# THTfeather.net
KiCad netlist of a schematic drawn in EAGLE
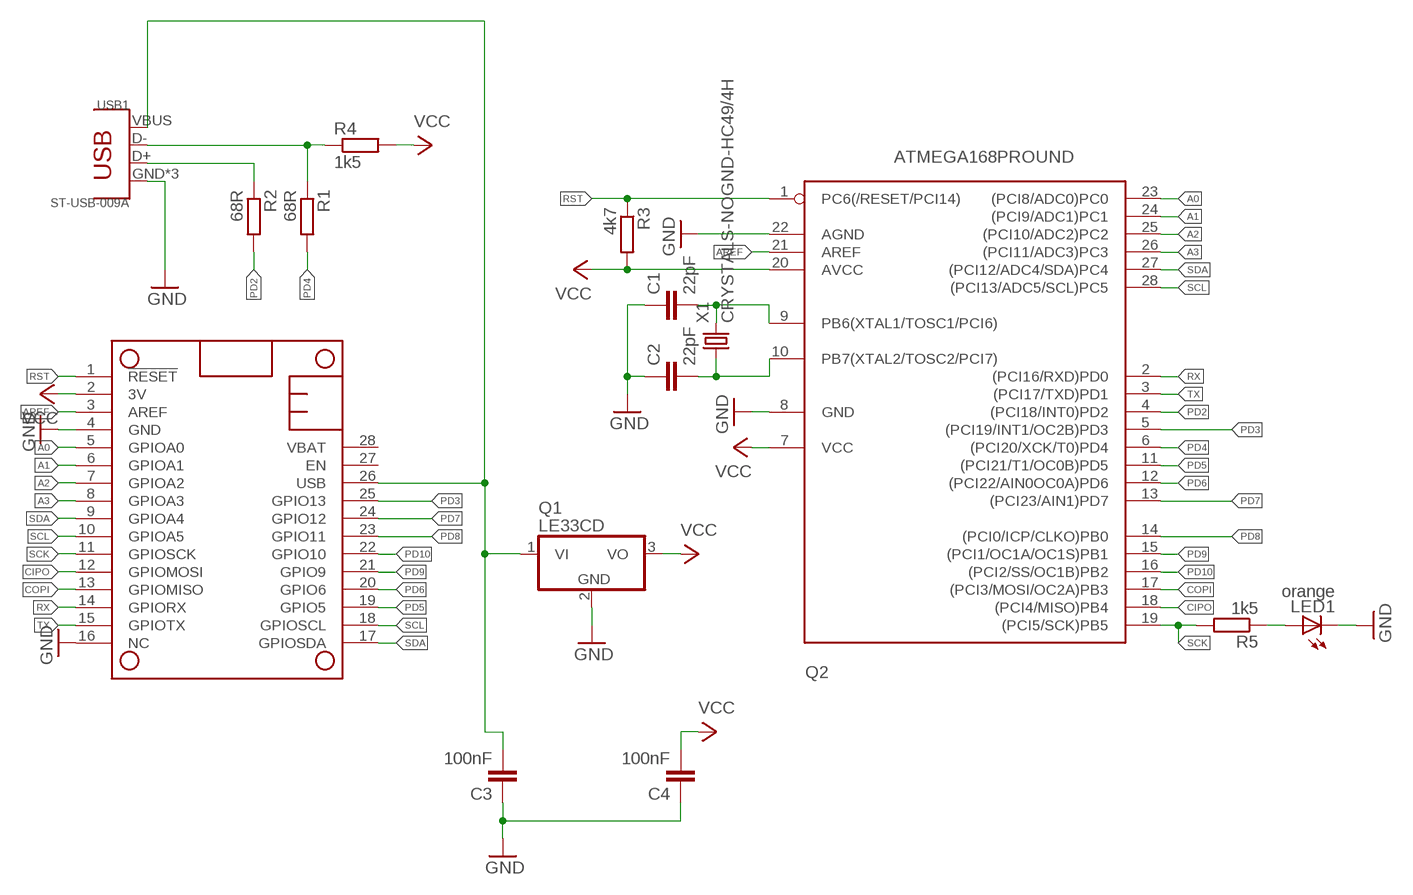
[diagram p0: schematic, sheet 1]

(export (version "E")
  (design (tool "Eeschema 10.0.6"))
  (components
    (comp (ref "C1")
      (value "22pF")
      (footprint "eagle-import:C025-025X050")
      (libsource (lib "eagle-import") (part "C-EU025-025X050"))
    )
    (comp (ref "C2")
      (value "22pF")
      (footprint "eagle-import:C025-025X050")
      (libsource (lib "eagle-import") (part "C-EU025-025X050"))
    )
    (comp (ref "C3")
      (value "100nF")
      (footprint "eagle-import:C025-025X050")
      (libsource (lib "eagle-import") (part "C-EU025-025X050"))
    )
    (comp (ref "C4")
      (value "100nF")
      (footprint "eagle-import:C025-025X050")
      (libsource (lib "eagle-import") (part "C-EU025-025X050"))
    )
    (comp (ref "LED1")
      (value "orange")
      (footprint "eagle-import:LED3MM")
      (libsource (lib "eagle-import") (part "LED3MM"))
    )
    (comp (ref "MS1")
      (value "FEATHERWING_NODIM")
      (footprint "eagle-import:FEATHERWING_DIM")
      (libsource (lib "eagle-import") (part "FEATHERWING_NODIM"))
    )
    (comp (ref "Q1")
      (value "LE33CD")
      (footprint "eagle-import:TO92")
      (libsource (lib "eagle-import") (part "78L33"))
    )
    (comp (ref "Q2")
      (value "ATMEGA168PROUND")
      (footprint "eagle-import:DIL28-3-ROUND")
      (libsource (lib "eagle-import") (part "ATMEGA168PROUND"))
    )
    (comp (ref "R1")
      (value "68R")
      (footprint "eagle-import:0204_5")
      (libsource (lib "eagle-import") (part "R-EU_0204/5"))
    )
    (comp (ref "R2")
      (value "68R")
      (footprint "eagle-import:0204_5")
      (libsource (lib "eagle-import") (part "R-EU_0204/5"))
    )
    (comp (ref "R3")
      (value "4k7")
      (footprint "eagle-import:0204_5")
      (libsource (lib "eagle-import") (part "R-EU_0204/5"))
    )
    (comp (ref "R4")
      (value "1k5")
      (footprint "eagle-import:0204_5")
      (libsource (lib "eagle-import") (part "R-EU_0204/5"))
    )
    (comp (ref "R5")
      (value "1k5")
      (footprint "eagle-import:0204_5")
      (libsource (lib "eagle-import") (part "R-EU_0204/5"))
    )
    (comp (ref "USB1")
      (value "ST-USB-009A")
      (footprint "eagle-import:USB4+2-2.5-90D")
      (libsource (lib "eagle-import") (part "DIP-USB-B-TYPE-FMAL(4+2P-2.5-90D)"))
    )
    (comp (ref "X1")
      (value "CRYSTALS-NOGND-HC49/4H")
      (footprint "eagle-import:HC49")
      (libsource (lib "eagle-import") (part "CRYSTALS-NOGND-HC49/4H"))
    )
  )
  (nets
    (net (code "1") (name "/VBAT") (class "Default")
      (node (ref "MS1") (pin "28") (pinfunction "VBAT_28") (pintype "power_in"))
    )
    (net (code "2") (name "A0") (class "Default")
      (node (ref "MS1") (pin "5") (pinfunction "GPIOA0_5") (pintype "bidirectional"))
      (node (ref "Q2") (pin "23") (pinfunction "(PCI8/ADC0)PC0_23") (pintype "bidirectional"))
    )
    (net (code "3") (name "A1") (class "Default")
      (node (ref "MS1") (pin "6") (pinfunction "GPIOA1_6") (pintype "bidirectional"))
      (node (ref "Q2") (pin "24") (pinfunction "(PCI9/ADC1)PC1_24") (pintype "bidirectional"))
    )
    (net (code "4") (name "A2") (class "Default")
      (node (ref "MS1") (pin "7") (pinfunction "GPIOA2_7") (pintype "bidirectional"))
      (node (ref "Q2") (pin "25") (pinfunction "(PCI10/ADC2)PC2_25") (pintype "bidirectional"))
    )
    (net (code "5") (name "A3") (class "Default")
      (node (ref "MS1") (pin "8") (pinfunction "GPIOA3_8") (pintype "bidirectional"))
      (node (ref "Q2") (pin "26") (pinfunction "(PCI11/ADC3)PC3_26") (pintype "bidirectional"))
    )
    (net (code "6") (name "AREF") (class "Default")
      (node (ref "MS1") (pin "3") (pinfunction "AREF_3") (pintype "passive"))
      (node (ref "Q2") (pin "21") (pinfunction "AREF_21") (pintype "bidirectional"))
    )
    (net (code "7") (name "CIPO") (class "Default")
      (node (ref "MS1") (pin "12") (pinfunction "GPIOMOSI_12") (pintype "bidirectional"))
      (node (ref "Q2") (pin "18") (pinfunction "(PCI4/MISO)PB4_18") (pintype "bidirectional"))
    )
    (net (code "8") (name "COPI") (class "Default")
      (node (ref "MS1") (pin "13") (pinfunction "GPIOMISO_13") (pintype "bidirectional"))
      (node (ref "Q2") (pin "17") (pinfunction "(PCI3/MOSI/OC2A)PB3_17") (pintype "bidirectional"))
    )
    (net (code "9") (name "GND") (class "Default")
      (node (ref "C1") (pin "1") (pinfunction "1_1") (pintype "passive"))
      (node (ref "C2") (pin "1") (pinfunction "1_1") (pintype "passive"))
      (node (ref "C3") (pin "1") (pinfunction "1_1") (pintype "passive"))
      (node (ref "C4") (pin "1") (pinfunction "1_1") (pintype "passive"))
      (node (ref "LED1") (pin "K") (pinfunction "C_K") (pintype "passive"))
      (node (ref "MS1") (pin "16") (pinfunction "NC_16") (pintype "passive"))
      (node (ref "MS1") (pin "4") (pinfunction "GND_4") (pintype "power_in"))
      (node (ref "Q1") (pin "2") (pinfunction "GND_2") (pintype "passive"))
      (node (ref "Q2") (pin "22") (pinfunction "AGND_22") (pintype "bidirectional"))
      (node (ref "Q2") (pin "8") (pinfunction "GND_8") (pintype "bidirectional"))
      (node (ref "USB1") (pin "GND") (pinfunction "4_GND") (pintype "bidirectional"))
      (node (ref "USB1") (pin "S1") (pinfunction "4_S1") (pintype "bidirectional"))
      (node (ref "USB1") (pin "S2") (pinfunction "4_S2") (pintype "bidirectional"))
    )
    (net (code "10") (name "Net-(LED1-PadA)") (class "Default")
      (node (ref "LED1") (pin "A") (pinfunction "A_A") (pintype "passive"))
      (node (ref "R5") (pin "1") (pinfunction "1_1") (pintype "passive"))
    )
    (net (code "11") (name "Net-(MS1-USB)") (class "Default")
      (node (ref "C3") (pin "2") (pinfunction "2_2") (pintype "passive"))
      (node (ref "MS1") (pin "26") (pinfunction "USB_26") (pintype "power_in"))
      (node (ref "Q1") (pin "1") (pinfunction "VI_1") (pintype "input"))
      (node (ref "USB1") (pin "VBUS") (pinfunction "1_VBUS") (pintype "bidirectional"))
    )
    (net (code "12") (name "Net-(Q2-PB6(XTAL1{slash}TOSC1{slash}PCI6))") (class "Default")
      (node (ref "C1") (pin "2") (pinfunction "2_2") (pintype "passive"))
      (node (ref "Q2") (pin "9") (pinfunction "PB6(XTAL1/TOSC1/PCI6)_9") (pintype "bidirectional"))
      (node (ref "X1") (pin "2") (pinfunction "2_2") (pintype "passive"))
    )
    (net (code "13") (name "Net-(Q2-PB7(XTAL2{slash}TOSC2{slash}PCI7))") (class "Default")
      (node (ref "C2") (pin "2") (pinfunction "2_2") (pintype "passive"))
      (node (ref "Q2") (pin "10") (pinfunction "PB7(XTAL2/TOSC2/PCI7)_10") (pintype "bidirectional"))
      (node (ref "X1") (pin "1") (pinfunction "1_1") (pintype "passive"))
    )
    (net (code "14") (name "Net-(USB1-2)") (class "Default")
      (node (ref "R1") (pin "1") (pinfunction "1_1") (pintype "passive"))
      (node (ref "R4") (pin "1") (pinfunction "1_1") (pintype "passive"))
      (node (ref "USB1") (pin "D-") (pinfunction "2_D-") (pintype "bidirectional"))
    )
    (net (code "15") (name "Net-(USB1-3)") (class "Default")
      (node (ref "R2") (pin "1") (pinfunction "1_1") (pintype "passive"))
      (node (ref "USB1") (pin "D+") (pinfunction "3_D+") (pintype "bidirectional"))
    )
    (net (code "16") (name "PD2") (class "Default")
      (node (ref "Q2") (pin "4") (pinfunction "(PCI18/INT0)PD2_4") (pintype "bidirectional"))
      (node (ref "R2") (pin "2") (pinfunction "2_2") (pintype "passive"))
    )
    (net (code "17") (name "PD3") (class "Default")
      (node (ref "MS1") (pin "25") (pinfunction "GPIO13_25") (pintype "bidirectional"))
      (node (ref "Q2") (pin "5") (pinfunction "(PCI19/INT1/OC2B)PD3_5") (pintype "bidirectional"))
    )
    (net (code "18") (name "PD4") (class "Default")
      (node (ref "Q2") (pin "6") (pinfunction "(PCI20/XCK/T0)PD4_6") (pintype "bidirectional"))
      (node (ref "R1") (pin "2") (pinfunction "2_2") (pintype "passive"))
    )
    (net (code "19") (name "PD5") (class "Default")
      (node (ref "MS1") (pin "19") (pinfunction "GPIO5_19") (pintype "bidirectional"))
      (node (ref "Q2") (pin "11") (pinfunction "(PCI21/T1/OC0B)PD5_11") (pintype "bidirectional"))
    )
    (net (code "20") (name "PD6") (class "Default")
      (node (ref "MS1") (pin "20") (pinfunction "GPIO6_20") (pintype "bidirectional"))
      (node (ref "Q2") (pin "12") (pinfunction "(PCI22/AIN0OC0A)PD6_12") (pintype "bidirectional"))
    )
    (net (code "21") (name "PD7") (class "Default")
      (node (ref "MS1") (pin "24") (pinfunction "GPIO12_24") (pintype "bidirectional"))
      (node (ref "Q2") (pin "13") (pinfunction "(PCI23/AIN1)PD7_13") (pintype "bidirectional"))
    )
    (net (code "22") (name "PD8") (class "Default")
      (node (ref "MS1") (pin "23") (pinfunction "GPIO11_23") (pintype "bidirectional"))
      (node (ref "Q2") (pin "14") (pinfunction "(PCI0/ICP/CLKO)PB0_14") (pintype "bidirectional"))
    )
    (net (code "23") (name "PD9") (class "Default")
      (node (ref "MS1") (pin "21") (pinfunction "GPIO9_21") (pintype "bidirectional"))
      (node (ref "Q2") (pin "15") (pinfunction "(PCI1/OC1A/OC1S)PB1_15") (pintype "bidirectional"))
    )
    (net (code "24") (name "PD10") (class "Default")
      (node (ref "MS1") (pin "22") (pinfunction "GPIO10_22") (pintype "bidirectional"))
      (node (ref "Q2") (pin "16") (pinfunction "(PCI2/SS/OC1B)PB2_16") (pintype "bidirectional"))
    )
    (net (code "25") (name "RST") (class "Default")
      (node (ref "MS1") (pin "1") (pinfunction "~{RESET}_1") (pintype "input"))
      (node (ref "Q2") (pin "1") (pinfunction "PC6(/RESET/PCI14)_1") (pintype "bidirectional"))
      (node (ref "R3") (pin "1") (pinfunction "1_1") (pintype "passive"))
    )
    (net (code "26") (name "RX") (class "Default")
      (node (ref "MS1") (pin "14") (pinfunction "GPIORX_14") (pintype "bidirectional"))
      (node (ref "Q2") (pin "2") (pinfunction "(PCI16/RXD)PD0_2") (pintype "bidirectional"))
    )
    (net (code "27") (name "SCK") (class "Default")
      (node (ref "MS1") (pin "11") (pinfunction "GPIOSCK_11") (pintype "bidirectional"))
      (node (ref "Q2") (pin "19") (pinfunction "(PCI5/SCK)PB5_19") (pintype "bidirectional"))
      (node (ref "R5") (pin "2") (pinfunction "2_2") (pintype "passive"))
    )
    (net (code "28") (name "SCL") (class "Default")
      (node (ref "MS1") (pin "10") (pinfunction "GPIOA5_10") (pintype "bidirectional"))
      (node (ref "MS1") (pin "18") (pinfunction "GPIOSCL_18") (pintype "bidirectional"))
      (node (ref "Q2") (pin "28") (pinfunction "(PCI13/ADC5/SCL)PC5_28") (pintype "bidirectional"))
    )
    (net (code "29") (name "SDA") (class "Default")
      (node (ref "MS1") (pin "17") (pinfunction "GPIOSDA_17") (pintype "bidirectional"))
      (node (ref "MS1") (pin "9") (pinfunction "GPIOA4_9") (pintype "bidirectional"))
      (node (ref "Q2") (pin "27") (pinfunction "(PCI12/ADC4/SDA)PC4_27") (pintype "bidirectional"))
    )
    (net (code "30") (name "TX") (class "Default")
      (node (ref "MS1") (pin "15") (pinfunction "GPIOTX_15") (pintype "bidirectional"))
      (node (ref "Q2") (pin "3") (pinfunction "(PCI17/TXD)PD1_3") (pintype "bidirectional"))
    )
    (net (code "31") (name "VCC") (class "Default")
      (node (ref "C4") (pin "2") (pinfunction "2_2") (pintype "passive"))
      (node (ref "MS1") (pin "2") (pinfunction "3V_2") (pintype "power_in"))
      (node (ref "Q1") (pin "3") (pinfunction "VO_3") (pintype "passive"))
      (node (ref "Q2") (pin "20") (pinfunction "AVCC_20") (pintype "bidirectional"))
      (node (ref "Q2") (pin "7") (pinfunction "VCC_7") (pintype "bidirectional"))
      (node (ref "R3") (pin "2") (pinfunction "2_2") (pintype "passive"))
      (node (ref "R4") (pin "2") (pinfunction "2_2") (pintype "passive"))
    )
    (net (code "32") (name "unconnected-(MS1-EN-Pad27)") (class "Default")
      (node (ref "MS1") (pin "27") (pinfunction "EN_27") (pintype "passive"))
    )
  )
)
